# Connector.net
KiCad netlist of a schematic drawn in Altium Designer
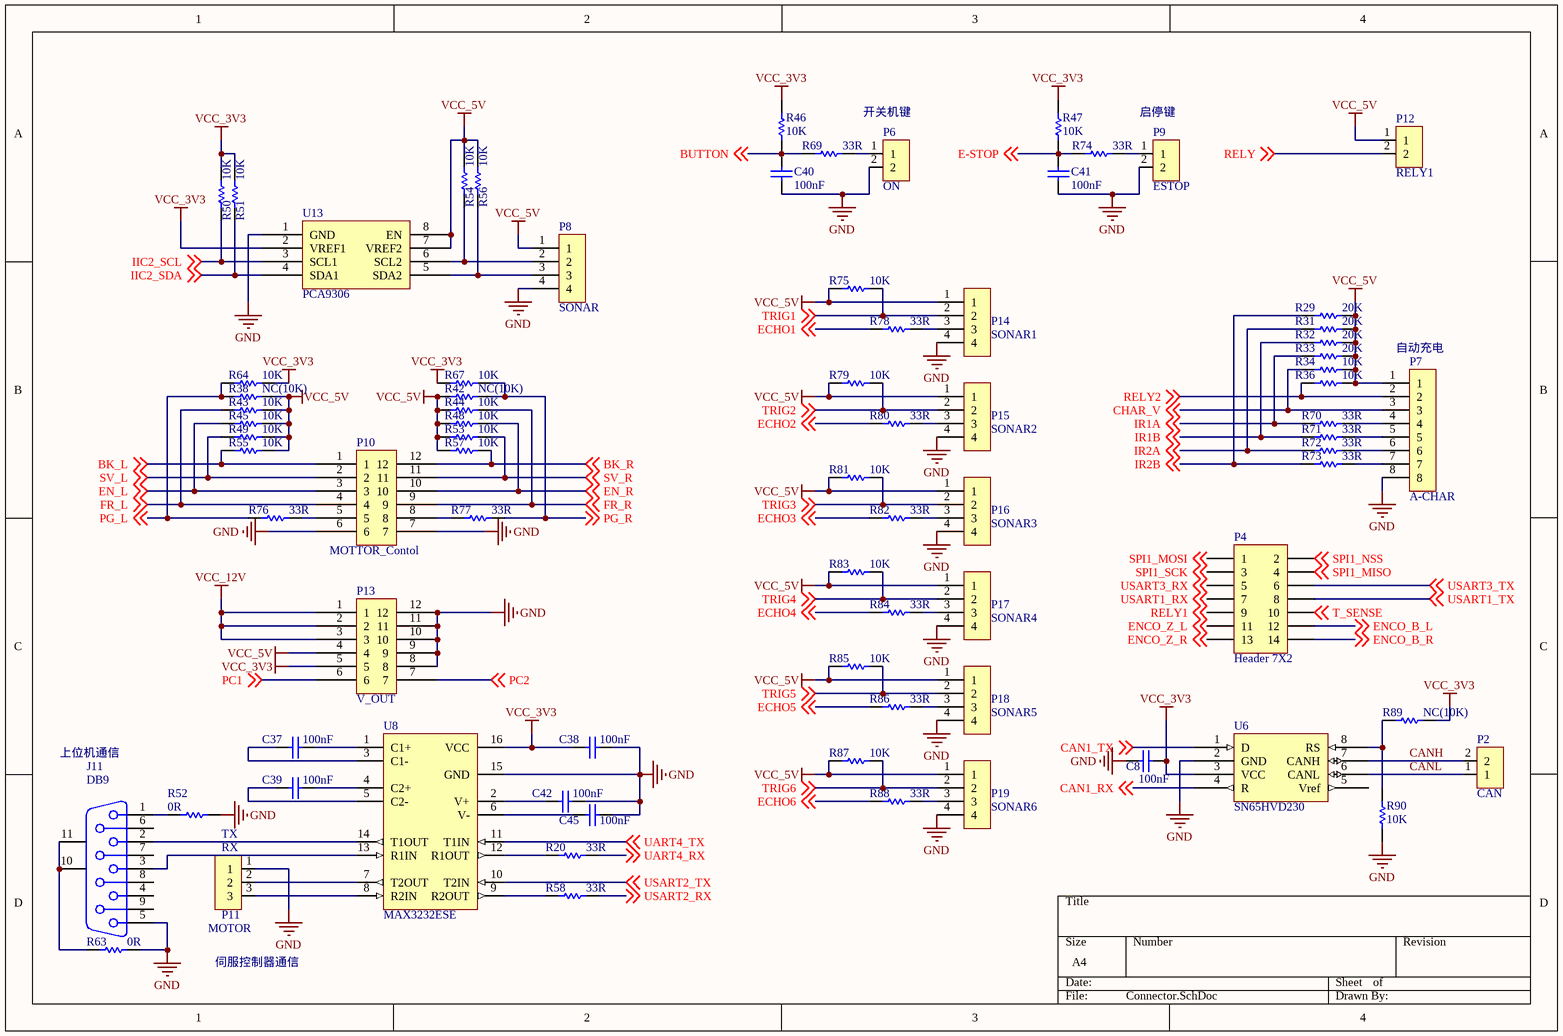
[diagram p0: Connector.SchDoc]

(export (version "E")
  (design (tool "Eeschema 10.0.6"))
  (components
    (comp (ref "C8")
      (value "100nF")
      (footprint "C0805")
      (description "Capacitor")
      (fields (field (name "Comment") "Cap") (field (name "PUBLISHER") "Altium Limited"))
      (libsource (lib "boocax_schlib") (part "Cap"))
    )
    (comp (ref "C37")
      (value "100nF")
      (footprint "C0805")
      (description "Capacitor")
      (fields (field (name "Comment") "Cap") (field (name "PUBLISHER") "Altium Limited"))
      (libsource (lib "boocax_schlib") (part "Cap"))
    )
    (comp (ref "C38")
      (value "100nF")
      (footprint "C0805")
      (description "Capacitor")
      (fields (field (name "Comment") "Cap") (field (name "PUBLISHER") "Altium Limited"))
      (libsource (lib "boocax_schlib") (part "Cap"))
    )
    (comp (ref "C39")
      (value "100nF")
      (footprint "C0805")
      (description "Capacitor")
      (fields (field (name "Comment") "Cap") (field (name "PUBLISHER") "Altium Limited"))
      (libsource (lib "boocax_schlib") (part "Cap"))
    )
    (comp (ref "C40")
      (value "100nF")
      (footprint "C0805")
      (description "Capacitor")
      (fields (field (name "Comment") "Cap") (field (name "PUBLISHER") "Altium Limited"))
      (libsource (lib "boocax_schlib") (part "Cap"))
    )
    (comp (ref "C41")
      (value "100nF")
      (footprint "C0805")
      (description "Capacitor")
      (fields (field (name "Comment") "Cap") (field (name "PUBLISHER") "Altium Limited"))
      (libsource (lib "boocax_schlib") (part "Cap"))
    )
    (comp (ref "C42")
      (value "100nF")
      (footprint "C0805")
      (description "Capacitor")
      (fields (field (name "Comment") "Cap") (field (name "PUBLISHER") "Altium Limited"))
      (libsource (lib "boocax_schlib") (part "Cap"))
    )
    (comp (ref "C45")
      (value "100nF")
      (footprint "C0805")
      (description "Capacitor")
      (fields (field (name "Comment") "Cap") (field (name "PUBLISHER") "Altium Limited"))
      (libsource (lib "boocax_schlib") (part "Cap"))
    )
    (comp (ref "J11")
      (value "DB9")
      (footprint "DB9-TH-F-Z")
      (description "串口")
      (fields (field (name "PUBLISHER") "Altium Limited"))
      (libsource (lib "founder") (part "D Connector 9"))
    )
    (comp (ref "P2")
      (value "CAN")
      (footprint "boocax_schlib:XH2.54-2P")
      (libsource (lib "") (part "Conn_1*2_1"))
    )
    (comp (ref "P4")
      (value "Header 7X2")
      (footprint "HDR2X7")
      (description "Header, 7-Pin, Dual row")
      (fields (field (name "PUBLISHER") "Altium Limited"))
      (libsource (lib "Miscellaneous Connectors") (part "Header 7X2"))
    )
    (comp (ref "P6")
      (value "ON")
      (footprint "boocax_schlib:XH2.54-2P")
      (libsource (lib "boocax_schlib") (part "Conn_1*2"))
    )
    (comp (ref "P7")
      (value "A-CHAR")
      (footprint "boocax_schlib:XH2.54-8P")
      (libsource (lib "boocax_schlib") (part "Conn_1*8"))
    )
    (comp (ref "P8")
      (value "SONAR")
      (footprint "boocax_schlib:XH2.54-4P")
      (libsource (lib "boocax_schlib") (part "Conn_1*4_1"))
    )
    (comp (ref "P9")
      (value "ESTOP")
      (footprint "boocax_schlib:XH2.54-2P")
      (libsource (lib "boocax_schlib") (part "Conn_1*2"))
    )
    (comp (ref "P10")
      (value "MOTTOR_Contol")
      (footprint "boocax_schlib:PORT-DIP2X6-3-LOCK")
      (libsource (lib "boocax_schlib") (part "Conn_2*6"))
    )
    (comp (ref "P11")
      (value "MOTOR")
      (footprint "boocax_schlib:XH2.54-3P")
      (libsource (lib "boocax_schlib") (part "Conn_1*3"))
    )
    (comp (ref "P12")
      (value "RELY1")
      (footprint "boocax_schlib:XH2.54-2P")
      (libsource (lib "boocax_schlib") (part "Conn_1*2"))
    )
    (comp (ref "P13")
      (value "V_OUT")
      (footprint "boocax_schlib:PORT-DIP2X6-3-LOCK")
      (libsource (lib "boocax_schlib") (part "Conn_2*6"))
    )
    (comp (ref "P14")
      (value "SONAR1")
      (footprint "boocax_schlib:XH2.54-4P")
      (libsource (lib "boocax_schlib") (part "Conn_1*4_1"))
    )
    (comp (ref "P15")
      (value "SONAR2")
      (footprint "boocax_schlib:XH2.54-4P")
      (libsource (lib "boocax_schlib") (part "Conn_1*4_1"))
    )
    (comp (ref "P16")
      (value "SONAR3")
      (footprint "boocax_schlib:XH2.54-4P")
      (libsource (lib "boocax_schlib") (part "Conn_1*4_1"))
    )
    (comp (ref "P17")
      (value "SONAR4")
      (footprint "boocax_schlib:XH2.54-4P")
      (libsource (lib "boocax_schlib") (part "Conn_1*4_1"))
    )
    (comp (ref "P18")
      (value "SONAR5")
      (footprint "boocax_schlib:XH2.54-4P")
      (libsource (lib "boocax_schlib") (part "Conn_1*4_1"))
    )
    (comp (ref "P19")
      (value "SONAR6")
      (footprint "boocax_schlib:XH2.54-4P")
      (libsource (lib "boocax_schlib") (part "Conn_1*4_1"))
    )
    (comp (ref "R20")
      (value "33R")
      (footprint "R0805")
      (description "Resistor")
      (fields (field (name "Comment") "Res1") (field (name "PUBLISHER") "Altium Limited"))
      (libsource (lib "boocax_schlib") (part "Res1"))
    )
    (comp (ref "R29")
      (value "20K")
      (footprint "R0805")
      (description "Resistor")
      (fields (field (name "Comment") "Res1") (field (name "PUBLISHER") "Altium Limited"))
      (libsource (lib "boocax_schlib") (part "Res1"))
    )
    (comp (ref "R31")
      (value "20K")
      (footprint "R0805")
      (description "Resistor")
      (fields (field (name "Comment") "Res1") (field (name "PUBLISHER") "Altium Limited"))
      (libsource (lib "boocax_schlib") (part "Res1"))
    )
    (comp (ref "R32")
      (value "20K")
      (footprint "R0805")
      (description "Resistor")
      (fields (field (name "Comment") "Res1") (field (name "PUBLISHER") "Altium Limited"))
      (libsource (lib "boocax_schlib") (part "Res1"))
    )
    (comp (ref "R33")
      (value "20K")
      (footprint "R0805")
      (description "Resistor")
      (fields (field (name "Comment") "Res1") (field (name "PUBLISHER") "Altium Limited"))
      (libsource (lib "boocax_schlib") (part "Res1"))
    )
    (comp (ref "R34")
      (value "10K")
      (footprint "R0805")
      (description "Resistor")
      (fields (field (name "Comment") "Res1") (field (name "PUBLISHER") "Altium Limited"))
      (libsource (lib "boocax_schlib") (part "Res1"))
    )
    (comp (ref "R36")
      (value "10K")
      (footprint "R0805")
      (description "Resistor")
      (fields (field (name "Comment") "Res1") (field (name "PUBLISHER") "Altium Limited"))
      (libsource (lib "boocax_schlib") (part "Res1"))
    )
    (comp (ref "R38")
      (value "NC(10K)")
      (footprint "R0805")
      (description "Resistor")
      (fields (field (name "Comment") "Res1") (field (name "PUBLISHER") "Altium Limited"))
      (libsource (lib "boocax_schlib") (part "Res1"))
    )
    (comp (ref "R42")
      (value "NC(10K)")
      (footprint "R0805")
      (description "Resistor")
      (fields (field (name "Comment") "Res1") (field (name "PUBLISHER") "Altium Limited"))
      (libsource (lib "boocax_schlib") (part "Res1"))
    )
    (comp (ref "R43")
      (value "10K")
      (footprint "R0805")
      (description "Resistor")
      (fields (field (name "Comment") "Res1") (field (name "PUBLISHER") "Altium Limited"))
      (libsource (lib "boocax_schlib") (part "Res1"))
    )
    (comp (ref "R44")
      (value "10K")
      (footprint "R0805")
      (description "Resistor")
      (fields (field (name "Comment") "Res1") (field (name "PUBLISHER") "Altium Limited"))
      (libsource (lib "boocax_schlib") (part "Res1"))
    )
    (comp (ref "R45")
      (value "10K")
      (footprint "R0805")
      (description "Resistor")
      (fields (field (name "Comment") "Res1") (field (name "PUBLISHER") "Altium Limited"))
      (libsource (lib "boocax_schlib") (part "Res1"))
    )
    (comp (ref "R46")
      (value "10K")
      (footprint "R0805")
      (description "Resistor")
      (fields (field (name "Comment") "Res1") (field (name "PUBLISHER") "Altium Limited"))
      (libsource (lib "boocax_schlib") (part "Res1"))
    )
    (comp (ref "R47")
      (value "10K")
      (footprint "R0805")
      (description "Resistor")
      (fields (field (name "Comment") "Res1") (field (name "PUBLISHER") "Altium Limited"))
      (libsource (lib "boocax_schlib") (part "Res1"))
    )
    (comp (ref "R48")
      (value "10K")
      (footprint "R0805")
      (description "Resistor")
      (fields (field (name "Comment") "Res1") (field (name "PUBLISHER") "Altium Limited"))
      (libsource (lib "boocax_schlib") (part "Res1"))
    )
    (comp (ref "R49")
      (value "10K")
      (footprint "R0805")
      (description "Resistor")
      (fields (field (name "Comment") "Res1") (field (name "PUBLISHER") "Altium Limited"))
      (libsource (lib "boocax_schlib") (part "Res1"))
    )
    (comp (ref "R50")
      (value "10K")
      (footprint "R0805")
      (description "Resistor")
      (fields (field (name "Comment") "Res1") (field (name "PUBLISHER") "Altium Limited"))
      (libsource (lib "boocax_schlib") (part "Res1"))
    )
    (comp (ref "R51")
      (value "10K")
      (footprint "R0805")
      (description "Resistor")
      (fields (field (name "Comment") "Res1") (field (name "PUBLISHER") "Altium Limited"))
      (libsource (lib "boocax_schlib") (part "Res1"))
    )
    (comp (ref "R52")
      (value "0R")
      (footprint "R0805")
      (description "Resistor")
      (fields (field (name "Comment") "Res1") (field (name "PUBLISHER") "Altium Limited"))
      (libsource (lib "boocax_schlib") (part "Res1"))
    )
    (comp (ref "R53")
      (value "10K")
      (footprint "R0805")
      (description "Resistor")
      (fields (field (name "Comment") "Res1") (field (name "PUBLISHER") "Altium Limited"))
      (libsource (lib "boocax_schlib") (part "Res1"))
    )
    (comp (ref "R54")
      (value "10K")
      (footprint "R0805")
      (description "Resistor")
      (fields (field (name "Comment") "Res1") (field (name "PUBLISHER") "Altium Limited"))
      (libsource (lib "boocax_schlib") (part "Res1"))
    )
    (comp (ref "R55")
      (value "10K")
      (footprint "R0805")
      (description "Resistor")
      (fields (field (name "Comment") "Res1") (field (name "PUBLISHER") "Altium Limited"))
      (libsource (lib "boocax_schlib") (part "Res1"))
    )
    (comp (ref "R56")
      (value "10K")
      (footprint "R0805")
      (description "Resistor")
      (fields (field (name "Comment") "Res1") (field (name "PUBLISHER") "Altium Limited"))
      (libsource (lib "boocax_schlib") (part "Res1"))
    )
    (comp (ref "R57")
      (value "10K")
      (footprint "R0805")
      (description "Resistor")
      (fields (field (name "Comment") "Res1") (field (name "PUBLISHER") "Altium Limited"))
      (libsource (lib "boocax_schlib") (part "Res1"))
    )
    (comp (ref "R58")
      (value "33R")
      (footprint "R0805")
      (description "Resistor")
      (fields (field (name "Comment") "Res1") (field (name "PUBLISHER") "Altium Limited"))
      (libsource (lib "boocax_schlib") (part "Res1"))
    )
    (comp (ref "R63")
      (value "0R")
      (footprint "R0805")
      (description "Resistor")
      (fields (field (name "Comment") "Res1") (field (name "PUBLISHER") "Altium Limited"))
      (libsource (lib "boocax_schlib") (part "Res1"))
    )
    (comp (ref "R64")
      (value "10K")
      (footprint "R0805")
      (description "Resistor")
      (fields (field (name "Comment") "Res1") (field (name "PUBLISHER") "Altium Limited"))
      (libsource (lib "boocax_schlib") (part "Res1"))
    )
    (comp (ref "R67")
      (value "10K")
      (footprint "R0805")
      (description "Resistor")
      (fields (field (name "Comment") "Res1") (field (name "PUBLISHER") "Altium Limited"))
      (libsource (lib "boocax_schlib") (part "Res1"))
    )
    (comp (ref "R69")
      (value "33R")
      (footprint "R0805")
      (description "Resistor")
      (fields (field (name "Comment") "Res1") (field (name "PUBLISHER") "Altium Limited"))
      (libsource (lib "boocax_schlib") (part "Res1"))
    )
    (comp (ref "R70")
      (value "33R")
      (footprint "R0805")
      (description "Resistor")
      (fields (field (name "Comment") "Res1") (field (name "PUBLISHER") "Altium Limited"))
      (libsource (lib "boocax_schlib") (part "Res1"))
    )
    (comp (ref "R71")
      (value "33R")
      (footprint "R0805")
      (description "Resistor")
      (fields (field (name "Comment") "Res1") (field (name "PUBLISHER") "Altium Limited"))
      (libsource (lib "boocax_schlib") (part "Res1"))
    )
    (comp (ref "R72")
      (value "33R")
      (footprint "R0805")
      (description "Resistor")
      (fields (field (name "Comment") "Res1") (field (name "PUBLISHER") "Altium Limited"))
      (libsource (lib "boocax_schlib") (part "Res1"))
    )
    (comp (ref "R73")
      (value "33R")
      (footprint "R0805")
      (description "Resistor")
      (fields (field (name "Comment") "Res1") (field (name "PUBLISHER") "Altium Limited"))
      (libsource (lib "boocax_schlib") (part "Res1"))
    )
    (comp (ref "R74")
      (value "33R")
      (footprint "R0805")
      (description "Resistor")
      (fields (field (name "Comment") "Res1") (field (name "PUBLISHER") "Altium Limited"))
      (libsource (lib "boocax_schlib") (part "Res1"))
    )
    (comp (ref "R75")
      (value "10K")
      (footprint "R0805")
      (description "Resistor")
      (fields (field (name "Comment") "Res1") (field (name "PUBLISHER") "Altium Limited"))
      (libsource (lib "boocax_schlib") (part "Res1"))
    )
    (comp (ref "R76")
      (value "33R")
      (footprint "R0805")
      (description "Resistor")
      (fields (field (name "Comment") "Res1") (field (name "PUBLISHER") "Altium Limited"))
      (libsource (lib "boocax_schlib") (part "Res1"))
    )
    (comp (ref "R77")
      (value "33R")
      (footprint "R0805")
      (description "Resistor")
      (fields (field (name "Comment") "Res1") (field (name "PUBLISHER") "Altium Limited"))
      (libsource (lib "boocax_schlib") (part "Res1"))
    )
    (comp (ref "R78")
      (value "33R")
      (footprint "R0805")
      (description "Resistor")
      (fields (field (name "Comment") "Res1") (field (name "PUBLISHER") "Altium Limited"))
      (libsource (lib "boocax_schlib") (part "Res1"))
    )
    (comp (ref "R79")
      (value "10K")
      (footprint "R0805")
      (description "Resistor")
      (fields (field (name "Comment") "Res1") (field (name "PUBLISHER") "Altium Limited"))
      (libsource (lib "boocax_schlib") (part "Res1"))
    )
    (comp (ref "R80")
      (value "33R")
      (footprint "R0805")
      (description "Resistor")
      (fields (field (name "Comment") "Res1") (field (name "PUBLISHER") "Altium Limited"))
      (libsource (lib "boocax_schlib") (part "Res1"))
    )
    (comp (ref "R81")
      (value "10K")
      (footprint "R0805")
      (description "Resistor")
      (fields (field (name "Comment") "Res1") (field (name "PUBLISHER") "Altium Limited"))
      (libsource (lib "boocax_schlib") (part "Res1"))
    )
    (comp (ref "R82")
      (value "33R")
      (footprint "R0805")
      (description "Resistor")
      (fields (field (name "Comment") "Res1") (field (name "PUBLISHER") "Altium Limited"))
      (libsource (lib "boocax_schlib") (part "Res1"))
    )
    (comp (ref "R83")
      (value "10K")
      (footprint "R0805")
      (description "Resistor")
      (fields (field (name "Comment") "Res1") (field (name "PUBLISHER") "Altium Limited"))
      (libsource (lib "boocax_schlib") (part "Res1"))
    )
    (comp (ref "R84")
      (value "33R")
      (footprint "R0805")
      (description "Resistor")
      (fields (field (name "Comment") "Res1") (field (name "PUBLISHER") "Altium Limited"))
      (libsource (lib "boocax_schlib") (part "Res1"))
    )
    (comp (ref "R85")
      (value "10K")
      (footprint "R0805")
      (description "Resistor")
      (fields (field (name "Comment") "Res1") (field (name "PUBLISHER") "Altium Limited"))
      (libsource (lib "boocax_schlib") (part "Res1"))
    )
    (comp (ref "R86")
      (value "33R")
      (footprint "R0805")
      (description "Resistor")
      (fields (field (name "Comment") "Res1") (field (name "PUBLISHER") "Altium Limited"))
      (libsource (lib "boocax_schlib") (part "Res1"))
    )
    (comp (ref "R87")
      (value "10K")
      (footprint "R0805")
      (description "Resistor")
      (fields (field (name "Comment") "Res1") (field (name "PUBLISHER") "Altium Limited"))
      (libsource (lib "boocax_schlib") (part "Res1"))
    )
    (comp (ref "R88")
      (value "33R")
      (footprint "R0805")
      (description "Resistor")
      (fields (field (name "Comment") "Res1") (field (name "PUBLISHER") "Altium Limited"))
      (libsource (lib "boocax_schlib") (part "Res1"))
    )
    (comp (ref "R89")
      (value "NC(10K)")
      (footprint "R0805")
      (description "Resistor")
      (fields (field (name "Comment") "Res1") (field (name "PUBLISHER") "Altium Limited"))
      (libsource (lib "boocax_schlib") (part "Res1"))
    )
    (comp (ref "R90")
      (value "10K")
      (footprint "R0805")
      (description "Resistor")
      (fields (field (name "Comment") "Res1") (field (name "PUBLISHER") "Altium Limited"))
      (libsource (lib "boocax_schlib") (part "Res1"))
    )
    (comp (ref "U6")
      (value "SN65HVD230")
      (footprint "boocax_schlib:SO8-SN65HVD230")
      (libsource (lib "boocax_schlib") (part "SN65HVD230D"))
    )
    (comp (ref "U8")
      (value "MAX3232ESE")
      (footprint "BABA03A1:SOP16")
      (description "+5V Powered, Multi-Channel RS-232 Driver/Receiver")
      (fields (field (name "PUBLISHER") "Altium Limited"))
      (libsource (lib "BABA03A-V1") (part "MAX3232ESE"))
    )
    (comp (ref "U13")
      (value "PCA9306")
      (footprint "boocax_schlib:ACS712-SOIC8")
      (libsource (lib "BABA03A-V1") (part "PCA9306"))
    )
  )
  (nets
    (net (code "1") (name "/CANH") (class "Default")
      (node (ref "P2") (pin "2") (pinfunction "2_2") (pintype "passive"))
      (node (ref "U6") (pin "7") (pinfunction "CANH_7") (pintype "bidirectional"))
    )
    (net (code "2") (name "/CANL") (class "Default")
      (node (ref "P2") (pin "1") (pinfunction "1_1") (pintype "passive"))
      (node (ref "U6") (pin "6") (pinfunction "CANL_6") (pintype "bidirectional"))
    )
    (net (code "3") (name "BK_L") (class "Default")
      (node (ref "P10") (pin "1") (pinfunction "1_1") (pintype "passive"))
      (node (ref "R55") (pin "1") (pinfunction "1_1") (pintype "passive"))
    )
    (net (code "4") (name "BK_R") (class "Default")
      (node (ref "P10") (pin "12") (pinfunction "12_12") (pintype "passive"))
      (node (ref "R57") (pin "2") (pinfunction "2_2") (pintype "passive"))
    )
    (net (code "5") (name "BUTTON") (class "Default")
      (node (ref "C40") (pin "1") (pinfunction "1_1") (pintype "passive"))
      (node (ref "R46") (pin "1") (pinfunction "1_1") (pintype "passive"))
      (node (ref "R69") (pin "2") (pinfunction "2_2") (pintype "passive"))
    )
    (net (code "6") (name "CAN1_RX") (class "Default")
      (node (ref "U6") (pin "4") (pinfunction "R_4") (pintype "output"))
    )
    (net (code "7") (name "CAN1_TX") (class "Default")
      (node (ref "U6") (pin "1") (pinfunction "D_1") (pintype "input"))
    )
    (net (code "8") (name "CHAR_V") (class "Default")
      (node (ref "P7") (pin "3") (pinfunction "3_3") (pintype "passive"))
      (node (ref "R34") (pin "2") (pinfunction "2_2") (pintype "passive"))
    )
    (net (code "9") (name "E-STOP") (class "Default")
      (node (ref "C41") (pin "1") (pinfunction "1_1") (pintype "passive"))
      (node (ref "R47") (pin "1") (pinfunction "1_1") (pintype "passive"))
      (node (ref "R74") (pin "2") (pinfunction "2_2") (pintype "passive"))
    )
    (net (code "10") (name "ECHO1") (class "Default")
      (node (ref "R78") (pin "2") (pinfunction "2_2") (pintype "passive"))
    )
    (net (code "11") (name "ECHO2") (class "Default")
      (node (ref "R80") (pin "2") (pinfunction "2_2") (pintype "passive"))
    )
    (net (code "12") (name "ECHO3") (class "Default")
      (node (ref "R82") (pin "2") (pinfunction "2_2") (pintype "passive"))
    )
    (net (code "13") (name "ECHO4") (class "Default")
      (node (ref "R84") (pin "2") (pinfunction "2_2") (pintype "passive"))
    )
    (net (code "14") (name "ECHO5") (class "Default")
      (node (ref "R86") (pin "2") (pinfunction "2_2") (pintype "passive"))
    )
    (net (code "15") (name "ECHO6") (class "Default")
      (node (ref "R88") (pin "2") (pinfunction "2_2") (pintype "passive"))
    )
    (net (code "16") (name "ENCO_B_L") (class "Default")
      (node (ref "P4") (pin "12") (pinfunction "12_12") (pintype "passive"))
    )
    (net (code "17") (name "ENCO_B_R") (class "Default")
      (node (ref "P4") (pin "14") (pinfunction "14_14") (pintype "passive"))
    )
    (net (code "18") (name "ENCO_Z_L") (class "Default")
      (node (ref "P4") (pin "11") (pinfunction "11_11") (pintype "passive"))
    )
    (net (code "19") (name "ENCO_Z_R") (class "Default")
      (node (ref "P4") (pin "13") (pinfunction "13_13") (pintype "passive"))
    )
    (net (code "20") (name "EN_L") (class "Default")
      (node (ref "P10") (pin "3") (pinfunction "3_3") (pintype "passive"))
      (node (ref "R45") (pin "1") (pinfunction "1_1") (pintype "passive"))
    )
    (net (code "21") (name "EN_R") (class "Default")
      (node (ref "P10") (pin "10") (pinfunction "10_10") (pintype "passive"))
      (node (ref "R48") (pin "2") (pinfunction "2_2") (pintype "passive"))
    )
    (net (code "22") (name "FR_L") (class "Default")
      (node (ref "P10") (pin "4") (pinfunction "4_4") (pintype "passive"))
      (node (ref "R43") (pin "1") (pinfunction "1_1") (pintype "passive"))
    )
    (net (code "23") (name "FR_R") (class "Default")
      (node (ref "P10") (pin "9") (pinfunction "9_9") (pintype "passive"))
      (node (ref "R44") (pin "2") (pinfunction "2_2") (pintype "passive"))
    )
    (net (code "24") (name "GND") (class "Default")
      (node (ref "C38") (pin "1") (pinfunction "1_1") (pintype "passive"))
      (node (ref "C40") (pin "2") (pinfunction "2_2") (pintype "passive"))
      (node (ref "C41") (pin "2") (pinfunction "2_2") (pintype "passive"))
      (node (ref "C42") (pin "1") (pinfunction "1_1") (pintype "passive"))
      (node (ref "C45") (pin "1") (pinfunction "1_1") (pintype "passive"))
      (node (ref "C8") (pin "1") (pinfunction "1_1") (pintype "passive"))
      (node (ref "J11") (pin "5") (pinfunction "5_5") (pintype "passive"))
      (node (ref "P10") (pin "6") (pinfunction "6_6") (pintype "passive"))
      (node (ref "P10") (pin "7") (pinfunction "7_7") (pintype "passive"))
      (node (ref "P11") (pin "1") (pinfunction "1_1") (pintype "passive"))
      (node (ref "P13") (pin "10") (pinfunction "10_10") (pintype "passive"))
      (node (ref "P13") (pin "11") (pinfunction "11_11") (pintype "passive"))
      (node (ref "P13") (pin "12") (pinfunction "12_12") (pintype "passive"))
      (node (ref "P13") (pin "8") (pinfunction "8_8") (pintype "passive"))
      (node (ref "P13") (pin "9") (pinfunction "9_9") (pintype "passive"))
      (node (ref "P14") (pin "4") (pinfunction "4_4") (pintype "passive"))
      (node (ref "P15") (pin "4") (pinfunction "4_4") (pintype "passive"))
      (node (ref "P16") (pin "4") (pinfunction "4_4") (pintype "passive"))
      (node (ref "P17") (pin "4") (pinfunction "4_4") (pintype "passive"))
      (node (ref "P18") (pin "4") (pinfunction "4_4") (pintype "passive"))
      (node (ref "P19") (pin "4") (pinfunction "4_4") (pintype "passive"))
      (node (ref "P6") (pin "2") (pinfunction "2_2") (pintype "passive"))
      (node (ref "P7") (pin "8") (pinfunction "8_8") (pintype "passive"))
      (node (ref "P8") (pin "4") (pinfunction "4_4") (pintype "passive"))
      (node (ref "P9") (pin "2") (pinfunction "2_2") (pintype "passive"))
      (node (ref "R52") (pin "1") (pinfunction "1_1") (pintype "passive"))
      (node (ref "R63") (pin "1") (pinfunction "1_1") (pintype "passive"))
      (node (ref "R90") (pin "2") (pinfunction "2_2") (pintype "passive"))
      (node (ref "U13") (pin "1") (pinfunction "GND_1") (pintype "passive"))
      (node (ref "U6") (pin "2") (pinfunction "GND_2") (pintype "power_in"))
      (node (ref "U8") (pin "15") (pinfunction "GND_15") (pintype "power_in"))
    )
    (net (code "25") (name "IIC2_SCL") (class "Default")
      (node (ref "R50") (pin "1") (pinfunction "1_1") (pintype "passive"))
      (node (ref "U13") (pin "3") (pinfunction "SCL1_3") (pintype "passive"))
    )
    (net (code "26") (name "IIC2_SDA") (class "Default")
      (node (ref "R51") (pin "1") (pinfunction "1_1") (pintype "passive"))
      (node (ref "U13") (pin "4") (pinfunction "SDA1_4") (pintype "passive"))
    )
    (net (code "27") (name "IR1A") (class "Default")
      (node (ref "R33") (pin "2") (pinfunction "2_2") (pintype "passive"))
      (node (ref "R70") (pin "2") (pinfunction "2_2") (pintype "passive"))
    )
    (net (code "28") (name "IR1B") (class "Default")
      (node (ref "R32") (pin "2") (pinfunction "2_2") (pintype "passive"))
      (node (ref "R71") (pin "2") (pinfunction "2_2") (pintype "passive"))
    )
    (net (code "29") (name "IR2A") (class "Default")
      (node (ref "R31") (pin "2") (pinfunction "2_2") (pintype "passive"))
      (node (ref "R72") (pin "2") (pinfunction "2_2") (pintype "passive"))
    )
    (net (code "30") (name "IR2B") (class "Default")
      (node (ref "R29") (pin "2") (pinfunction "2_2") (pintype "passive"))
      (node (ref "R73") (pin "2") (pinfunction "2_2") (pintype "passive"))
    )
    (net (code "31") (name "Net-(J11-MH1)") (class "Default")
      (node (ref "J11") (pin "10") (pinfunction "MH1_10") (pintype "passive"))
      (node (ref "J11") (pin "11") (pinfunction "MH2_11") (pintype "passive"))
      (node (ref "R63") (pin "2") (pinfunction "2_2") (pintype "passive"))
    )
    (net (code "32") (name "Net-(J11-Pad1)") (class "Default")
      (node (ref "J11") (pin "1") (pinfunction "1_1") (pintype "passive"))
      (node (ref "R52") (pin "2") (pinfunction "2_2") (pintype "passive"))
    )
    (net (code "33") (name "Net-(P6-Pad1)") (class "Default")
      (node (ref "P6") (pin "1") (pinfunction "1_1") (pintype "passive"))
      (node (ref "R69") (pin "1") (pinfunction "1_1") (pintype "passive"))
    )
    (net (code "34") (name "Net-(P7-Pad4)") (class "Default")
      (node (ref "P7") (pin "4") (pinfunction "4_4") (pintype "passive"))
      (node (ref "R70") (pin "1") (pinfunction "1_1") (pintype "passive"))
    )
    (net (code "35") (name "Net-(P7-Pad5)") (class "Default")
      (node (ref "P7") (pin "5") (pinfunction "5_5") (pintype "passive"))
      (node (ref "R71") (pin "1") (pinfunction "1_1") (pintype "passive"))
    )
    (net (code "36") (name "Net-(P7-Pad6)") (class "Default")
      (node (ref "P7") (pin "6") (pinfunction "6_6") (pintype "passive"))
      (node (ref "R72") (pin "1") (pinfunction "1_1") (pintype "passive"))
    )
    (net (code "37") (name "Net-(P7-Pad7)") (class "Default")
      (node (ref "P7") (pin "7") (pinfunction "7_7") (pintype "passive"))
      (node (ref "R73") (pin "1") (pinfunction "1_1") (pintype "passive"))
    )
    (net (code "38") (name "Net-(P9-Pad1)") (class "Default")
      (node (ref "P9") (pin "1") (pinfunction "1_1") (pintype "passive"))
      (node (ref "R74") (pin "1") (pinfunction "1_1") (pintype "passive"))
    )
    (net (code "39") (name "Net-(P10-Pad5)") (class "Default")
      (node (ref "P10") (pin "5") (pinfunction "5_5") (pintype "passive"))
      (node (ref "R76") (pin "1") (pinfunction "1_1") (pintype "passive"))
    )
    (net (code "40") (name "Net-(P10-Pad8)") (class "Default")
      (node (ref "P10") (pin "8") (pinfunction "8_8") (pintype "passive"))
      (node (ref "R77") (pin "2") (pinfunction "2_2") (pintype "passive"))
    )
    (net (code "41") (name "Net-(P14-Pad3)") (class "Default")
      (node (ref "P14") (pin "3") (pinfunction "3_3") (pintype "passive"))
      (node (ref "R78") (pin "1") (pinfunction "1_1") (pintype "passive"))
    )
    (net (code "42") (name "Net-(P15-Pad3)") (class "Default")
      (node (ref "P15") (pin "3") (pinfunction "3_3") (pintype "passive"))
      (node (ref "R80") (pin "1") (pinfunction "1_1") (pintype "passive"))
    )
    (net (code "43") (name "Net-(P16-Pad3)") (class "Default")
      (node (ref "P16") (pin "3") (pinfunction "3_3") (pintype "passive"))
      (node (ref "R82") (pin "1") (pinfunction "1_1") (pintype "passive"))
    )
    (net (code "44") (name "Net-(P17-Pad3)") (class "Default")
      (node (ref "P17") (pin "3") (pinfunction "3_3") (pintype "passive"))
      (node (ref "R84") (pin "1") (pinfunction "1_1") (pintype "passive"))
    )
    (net (code "45") (name "Net-(P18-Pad3)") (class "Default")
      (node (ref "P18") (pin "3") (pinfunction "3_3") (pintype "passive"))
      (node (ref "R86") (pin "1") (pinfunction "1_1") (pintype "passive"))
    )
    (net (code "46") (name "Net-(P19-Pad3)") (class "Default")
      (node (ref "P19") (pin "3") (pinfunction "3_3") (pintype "passive"))
      (node (ref "R88") (pin "1") (pinfunction "1_1") (pintype "passive"))
    )
    (net (code "47") (name "Net-(U6-RS)") (class "Default")
      (node (ref "R89") (pin "2") (pinfunction "2_2") (pintype "passive"))
      (node (ref "R90") (pin "1") (pinfunction "1_1") (pintype "passive"))
      (node (ref "U6") (pin "8") (pinfunction "RS_8") (pintype "input"))
    )
    (net (code "48") (name "Net-(U8-C1+)") (class "Default")
      (node (ref "C37") (pin "1") (pinfunction "1_1") (pintype "passive"))
      (node (ref "U8") (pin "1") (pinfunction "C1+_1") (pintype "passive"))
    )
    (net (code "49") (name "Net-(U8-C1-)") (class "Default")
      (node (ref "C37") (pin "2") (pinfunction "2_2") (pintype "passive"))
      (node (ref "U8") (pin "3") (pinfunction "C1-_3") (pintype "passive"))
    )
    (net (code "50") (name "Net-(U8-C2+)") (class "Default")
      (node (ref "C39") (pin "1") (pinfunction "1_1") (pintype "passive"))
      (node (ref "U8") (pin "4") (pinfunction "C2+_4") (pintype "passive"))
    )
    (net (code "51") (name "Net-(U8-C2-)") (class "Default")
      (node (ref "C39") (pin "2") (pinfunction "2_2") (pintype "passive"))
      (node (ref "U8") (pin "5") (pinfunction "C2-_5") (pintype "passive"))
    )
    (net (code "52") (name "Net-(U8-R1IN)") (class "Default")
      (node (ref "J11") (pin "3") (pinfunction "3_3") (pintype "passive"))
      (node (ref "U8") (pin "13") (pinfunction "R1IN_13") (pintype "input"))
    )
    (net (code "53") (name "Net-(U8-R1OUT)") (class "Default")
      (node (ref "R20") (pin "1") (pinfunction "1_1") (pintype "passive"))
      (node (ref "U8") (pin "12") (pinfunction "R1OUT_12") (pintype "output"))
    )
    (net (code "54") (name "Net-(U8-R2IN)") (class "Default")
      (node (ref "P11") (pin "3") (pinfunction "3_3") (pintype "passive"))
      (node (ref "U8") (pin "8") (pinfunction "R2IN_8") (pintype "input"))
    )
    (net (code "55") (name "Net-(U8-R2OUT)") (class "Default")
      (node (ref "R58") (pin "1") (pinfunction "1_1") (pintype "passive"))
      (node (ref "U8") (pin "9") (pinfunction "R2OUT_9") (pintype "output"))
    )
    (net (code "56") (name "Net-(U8-T1OUT)") (class "Default")
      (node (ref "J11") (pin "2") (pinfunction "2_2") (pintype "passive"))
      (node (ref "U8") (pin "14") (pinfunction "T1OUT_14") (pintype "output"))
    )
    (net (code "57") (name "Net-(U8-T2OUT)") (class "Default")
      (node (ref "P11") (pin "2") (pinfunction "2_2") (pintype "passive"))
      (node (ref "U8") (pin "7") (pinfunction "T2OUT_7") (pintype "output"))
    )
    (net (code "58") (name "Net-(U8-V+)") (class "Default")
      (node (ref "C42") (pin "2") (pinfunction "2_2") (pintype "passive"))
      (node (ref "U8") (pin "2") (pinfunction "V+_2") (pintype "power_in"))
    )
    (net (code "59") (name "Net-(U8-V-)") (class "Default")
      (node (ref "C45") (pin "2") (pinfunction "2_2") (pintype "passive"))
      (node (ref "U8") (pin "6") (pinfunction "V-_6") (pintype "power_in"))
    )
    (net (code "60") (name "Net-(U13-SCL2)") (class "Default")
      (node (ref "P8") (pin "2") (pinfunction "2_2") (pintype "passive"))
      (node (ref "R54") (pin "2") (pinfunction "2_2") (pintype "passive"))
      (node (ref "U13") (pin "6") (pinfunction "SCL2_6") (pintype "passive"))
    )
    (net (code "61") (name "Net-(U13-SDA2)") (class "Default")
      (node (ref "P8") (pin "3") (pinfunction "3_3") (pintype "passive"))
      (node (ref "R56") (pin "2") (pinfunction "2_2") (pintype "passive"))
      (node (ref "U13") (pin "5") (pinfunction "SDA2_5") (pintype "passive"))
    )
    (net (code "62") (name "PC1") (class "Default")
      (node (ref "P13") (pin "6") (pinfunction "6_6") (pintype "passive"))
    )
    (net (code "63") (name "PC2") (class "Default")
      (node (ref "P13") (pin "7") (pinfunction "7_7") (pintype "passive"))
    )
    (net (code "64") (name "PG_L") (class "Default")
      (node (ref "R38") (pin "1") (pinfunction "1_1") (pintype "passive"))
      (node (ref "R64") (pin "1") (pinfunction "1_1") (pintype "passive"))
      (node (ref "R76") (pin "2") (pinfunction "2_2") (pintype "passive"))
    )
    (net (code "65") (name "PG_R") (class "Default")
      (node (ref "R42") (pin "2") (pinfunction "2_2") (pintype "passive"))
      (node (ref "R67") (pin "2") (pinfunction "2_2") (pintype "passive"))
      (node (ref "R77") (pin "1") (pinfunction "1_1") (pintype "passive"))
    )
    (net (code "66") (name "RELY") (class "Default")
      (node (ref "P12") (pin "2") (pinfunction "2_2") (pintype "passive"))
    )
    (net (code "67") (name "RELY1") (class "Default")
      (node (ref "P4") (pin "9") (pinfunction "9_9") (pintype "passive"))
    )
    (net (code "68") (name "RELY2") (class "Default")
      (node (ref "P7") (pin "2") (pinfunction "2_2") (pintype "passive"))
      (node (ref "R36") (pin "2") (pinfunction "2_2") (pintype "passive"))
    )
    (net (code "69") (name "SPI1_MISO") (class "Default")
      (node (ref "P4") (pin "4") (pinfunction "4_4") (pintype "passive"))
    )
    (net (code "70") (name "SPI1_MOSI") (class "Default")
      (node (ref "P4") (pin "1") (pinfunction "1_1") (pintype "passive"))
    )
    (net (code "71") (name "SPI1_NSS") (class "Default")
      (node (ref "P4") (pin "2") (pinfunction "2_2") (pintype "passive"))
    )
    (net (code "72") (name "SPI1_SCK") (class "Default")
      (node (ref "P4") (pin "3") (pinfunction "3_3") (pintype "passive"))
    )
    (net (code "73") (name "SV_L") (class "Default")
      (node (ref "P10") (pin "2") (pinfunction "2_2") (pintype "passive"))
      (node (ref "R49") (pin "1") (pinfunction "1_1") (pintype "passive"))
    )
    (net (code "74") (name "SV_R") (class "Default")
      (node (ref "P10") (pin "11") (pinfunction "11_11") (pintype "passive"))
      (node (ref "R53") (pin "2") (pinfunction "2_2") (pintype "passive"))
    )
    (net (code "75") (name "TRIG1") (class "Default")
      (node (ref "P14") (pin "2") (pinfunction "2_2") (pintype "passive"))
      (node (ref "R75") (pin "1") (pinfunction "1_1") (pintype "passive"))
    )
    (net (code "76") (name "TRIG2") (class "Default")
      (node (ref "P15") (pin "2") (pinfunction "2_2") (pintype "passive"))
      (node (ref "R79") (pin "1") (pinfunction "1_1") (pintype "passive"))
    )
    (net (code "77") (name "TRIG3") (class "Default")
      (node (ref "P16") (pin "2") (pinfunction "2_2") (pintype "passive"))
      (node (ref "R81") (pin "1") (pinfunction "1_1") (pintype "passive"))
    )
    (net (code "78") (name "TRIG4") (class "Default")
      (node (ref "P17") (pin "2") (pinfunction "2_2") (pintype "passive"))
      (node (ref "R83") (pin "1") (pinfunction "1_1") (pintype "passive"))
    )
    (net (code "79") (name "TRIG5") (class "Default")
      (node (ref "P18") (pin "2") (pinfunction "2_2") (pintype "passive"))
      (node (ref "R85") (pin "1") (pinfunction "1_1") (pintype "passive"))
    )
    (net (code "80") (name "TRIG6") (class "Default")
      (node (ref "P19") (pin "2") (pinfunction "2_2") (pintype "passive"))
      (node (ref "R87") (pin "1") (pinfunction "1_1") (pintype "passive"))
    )
    (net (code "81") (name "T_SENSE") (class "Default")
      (node (ref "P4") (pin "10") (pinfunction "10_10") (pintype "passive"))
    )
    (net (code "82") (name "UART4_RX") (class "Default")
      (node (ref "R20") (pin "2") (pinfunction "2_2") (pintype "passive"))
    )
    (net (code "83") (name "UART4_TX") (class "Default")
      (node (ref "U8") (pin "11") (pinfunction "T1IN_11") (pintype "input"))
    )
    (net (code "84") (name "USART1_RX") (class "Default")
      (node (ref "P4") (pin "7") (pinfunction "7_7") (pintype "passive"))
    )
    (net (code "85") (name "USART1_TX") (class "Default")
      (node (ref "P4") (pin "8") (pinfunction "8_8") (pintype "passive"))
    )
    (net (code "86") (name "USART2_RX") (class "Default")
      (node (ref "R58") (pin "2") (pinfunction "2_2") (pintype "passive"))
    )
    (net (code "87") (name "USART2_TX") (class "Default")
      (node (ref "U8") (pin "10") (pinfunction "T2IN_10") (pintype "input"))
    )
    (net (code "88") (name "USART3_RX") (class "Default")
      (node (ref "P4") (pin "5") (pinfunction "5_5") (pintype "passive"))
    )
    (net (code "89") (name "USART3_TX") (class "Default")
      (node (ref "P4") (pin "6") (pinfunction "6_6") (pintype "passive"))
    )
    (net (code "90") (name "VCC_3V3") (class "Default")
      (node (ref "C38") (pin "2") (pinfunction "2_2") (pintype "passive"))
      (node (ref "C8") (pin "2") (pinfunction "2_2") (pintype "passive"))
      (node (ref "P13") (pin "5") (pinfunction "5_5") (pintype "passive"))
      (node (ref "R46") (pin "2") (pinfunction "2_2") (pintype "passive"))
      (node (ref "R47") (pin "2") (pinfunction "2_2") (pintype "passive"))
      (node (ref "R50") (pin "2") (pinfunction "2_2") (pintype "passive"))
      (node (ref "R51") (pin "2") (pinfunction "2_2") (pintype "passive"))
      (node (ref "R64") (pin "2") (pinfunction "2_2") (pintype "passive"))
      (node (ref "R67") (pin "1") (pinfunction "1_1") (pintype "passive"))
      (node (ref "R89") (pin "1") (pinfunction "1_1") (pintype "passive"))
      (node (ref "U13") (pin "2") (pinfunction "VREF1_2") (pintype "passive"))
      (node (ref "U6") (pin "3") (pinfunction "VCC_3") (pintype "power_in"))
      (node (ref "U8") (pin "16") (pinfunction "VCC_16") (pintype "power_in"))
    )
    (net (code "91") (name "VCC_5V") (class "Default")
      (node (ref "P12") (pin "1") (pinfunction "1_1") (pintype "passive"))
      (node (ref "P13") (pin "4") (pinfunction "4_4") (pintype "passive"))
      (node (ref "P14") (pin "1") (pinfunction "1_1") (pintype "passive"))
      (node (ref "P15") (pin "1") (pinfunction "1_1") (pintype "passive"))
      (node (ref "P16") (pin "1") (pinfunction "1_1") (pintype "passive"))
      (node (ref "P17") (pin "1") (pinfunction "1_1") (pintype "passive"))
      (node (ref "P18") (pin "1") (pinfunction "1_1") (pintype "passive"))
      (node (ref "P19") (pin "1") (pinfunction "1_1") (pintype "passive"))
      (node (ref "P7") (pin "1") (pinfunction "1_1") (pintype "passive"))
      (node (ref "P8") (pin "1") (pinfunction "1_1") (pintype "passive"))
      (node (ref "R29") (pin "1") (pinfunction "1_1") (pintype "passive"))
      (node (ref "R31") (pin "1") (pinfunction "1_1") (pintype "passive"))
      (node (ref "R32") (pin "1") (pinfunction "1_1") (pintype "passive"))
      (node (ref "R33") (pin "1") (pinfunction "1_1") (pintype "passive"))
      (node (ref "R34") (pin "1") (pinfunction "1_1") (pintype "passive"))
      (node (ref "R36") (pin "1") (pinfunction "1_1") (pintype "passive"))
      (node (ref "R38") (pin "2") (pinfunction "2_2") (pintype "passive"))
      (node (ref "R42") (pin "1") (pinfunction "1_1") (pintype "passive"))
      (node (ref "R43") (pin "2") (pinfunction "2_2") (pintype "passive"))
      (node (ref "R44") (pin "1") (pinfunction "1_1") (pintype "passive"))
      (node (ref "R45") (pin "2") (pinfunction "2_2") (pintype "passive"))
      (node (ref "R48") (pin "1") (pinfunction "1_1") (pintype "passive"))
      (node (ref "R49") (pin "2") (pinfunction "2_2") (pintype "passive"))
      (node (ref "R53") (pin "1") (pinfunction "1_1") (pintype "passive"))
      (node (ref "R54") (pin "1") (pinfunction "1_1") (pintype "passive"))
      (node (ref "R55") (pin "2") (pinfunction "2_2") (pintype "passive"))
      (node (ref "R56") (pin "1") (pinfunction "1_1") (pintype "passive"))
      (node (ref "R57") (pin "1") (pinfunction "1_1") (pintype "passive"))
      (node (ref "R75") (pin "2") (pinfunction "2_2") (pintype "passive"))
      (node (ref "R79") (pin "2") (pinfunction "2_2") (pintype "passive"))
      (node (ref "R81") (pin "2") (pinfunction "2_2") (pintype "passive"))
      (node (ref "R83") (pin "2") (pinfunction "2_2") (pintype "passive"))
      (node (ref "R85") (pin "2") (pinfunction "2_2") (pintype "passive"))
      (node (ref "R87") (pin "2") (pinfunction "2_2") (pintype "passive"))
      (node (ref "U13") (pin "7") (pinfunction "VREF2_7") (pintype "passive"))
      (node (ref "U13") (pin "8") (pinfunction "EN_8") (pintype "passive"))
    )
    (net (code "92") (name "VCC_12V") (class "Default")
      (node (ref "P13") (pin "1") (pinfunction "1_1") (pintype "passive"))
      (node (ref "P13") (pin "2") (pinfunction "2_2") (pintype "passive"))
      (node (ref "P13") (pin "3") (pinfunction "3_3") (pintype "passive"))
    )
    (net (code "93") (name "unconnected-(J11-Pad4)") (class "Default")
      (node (ref "J11") (pin "4") (pinfunction "4_4") (pintype "passive"))
    )
    (net (code "94") (name "unconnected-(J11-Pad6)") (class "Default")
      (node (ref "J11") (pin "6") (pinfunction "6_6") (pintype "passive"))
    )
    (net (code "95") (name "unconnected-(J11-Pad7)") (class "Default")
      (node (ref "J11") (pin "7") (pinfunction "7_7") (pintype "passive"))
    )
    (net (code "96") (name "unconnected-(J11-Pad8)") (class "Default")
      (node (ref "J11") (pin "8") (pinfunction "8_8") (pintype "passive"))
    )
    (net (code "97") (name "unconnected-(J11-Pad9)") (class "Default")
      (node (ref "J11") (pin "9") (pinfunction "9_9") (pintype "passive"))
    )
    (net (code "98") (name "unconnected-(U6-Vref-Pad5)") (class "Default")
      (node (ref "U6") (pin "5") (pinfunction "Vref_5") (pintype "output"))
    )
  )
)
